# boxing.net
KiCad netlist of a schematic drawn in Altium Designer
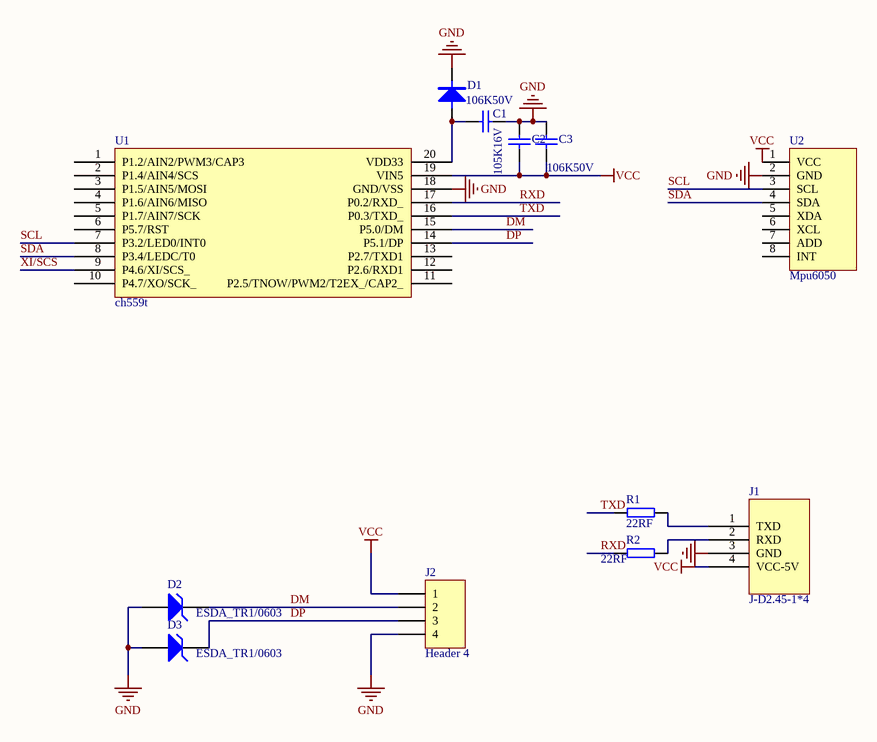
[diagram p0: boxing.SchDoc]

(export (version "E")
  (design (tool "Eeschema 10.0.6"))
  (components
    (comp (ref "C1")
      (value "106K50V")
      (footprint "C0603")
      (description "贴片电容-陶瓷")
      (libsource (lib "Capacitor") (part "C0603X7R-106K50V"))
    )
    (comp (ref "C2")
      (value "105K16V")
      (footprint "C0603")
      (description "贴片电容-陶瓷")
      (libsource (lib "Capacitor") (part "C0603X7R-105K16V"))
    )
    (comp (ref "C3")
      (value "106K50V")
      (footprint "C0603")
      (description "贴片电容-陶瓷")
      (libsource (lib "Capacitor") (part "C0603X7R-106K50V"))
    )
    (comp (ref "D1")
      (value "500mA/13.2V")
      (footprint "D1206")
      (description "500mA/13.2V 自恢复保险丝")
      (libsource (lib "Diode") (part "1206MSD"))
    )
    (comp (ref "D2")
      (value "ESDA_TR1/0603")
      (footprint "HS_0603D")
      (description "Zener Diode")
      (fields (field (name "PUBLISHER") "*"))
      (libsource (lib "HSC32K1(QFN56)_BlueTooth_V2.0_20171108 - 副本") (part "D Zener"))
    )
    (comp (ref "D3")
      (value "ESDA_TR1/0603")
      (footprint "HS_0603D")
      (description "Zener Diode")
      (fields (field (name "PUBLISHER") "*"))
      (libsource (lib "HSC32K1(QFN56)_BlueTooth_V2.0_20171108 - 副本") (part "D Zener"))
    )
    (comp (ref "J1")
      (value "J-D2.45-1*4")
      (footprint "D2.54-1*4P")
      (libsource (lib "Connector") (part "J-D2.54-1*4单排排母"))
    )
    (comp (ref "J2")
      (value "Header 4")
      (footprint "USB-AB")
      (description "Header, 4-Pin")
      (fields (field (name "PUBLISHER") "Altium Limited"))
      (libsource (lib "Miscellaneous Connectors") (part "Header 4"))
    )
    (comp (ref "R1")
      (value "22RF")
      (footprint "R0603")
      (description "贴片电阻-通用")
      (libsource (lib "Resistor") (part "R0603-22RF"))
    )
    (comp (ref "R2")
      (value "22RF")
      (footprint "R0603")
      (description "贴片电阻-通用")
      (libsource (lib "Resistor") (part "R0603-22RF"))
    )
    (comp (ref "U1")
      (value "ch559t")
      (footprint "SSOP-20")
      (description "CH559T-20pin")
      (libsource (lib "IC") (part "CH559T"))
    )
    (comp (ref "U2") (value "Mpu6050") (libsource (lib "IC") (part "Mpu6050")))
  )
  (nets
    (net (code "1") (name "/DM") (class "Default")
      (node (ref "D2") (pin "2") (pinfunction "K_2") (pintype "passive"))
      (node (ref "J2") (pin "2") (pinfunction "2_2") (pintype "passive"))
      (node (ref "U1") (pin "15") (pinfunction "P5.0/DM_15") (pintype "passive"))
    )
    (net (code "2") (name "/DP") (class "Default")
      (node (ref "D3") (pin "2") (pinfunction "K_2") (pintype "passive"))
      (node (ref "J2") (pin "3") (pinfunction "3_3") (pintype "passive"))
      (node (ref "U1") (pin "14") (pinfunction "P5.1/DP_14") (pintype "passive"))
    )
    (net (code "3") (name "/RXD") (class "Default")
      (node (ref "R2") (pin "2") (pinfunction "2_2") (pintype "passive"))
      (node (ref "U1") (pin "17") (pinfunction "P0.2/RXD__17") (pintype "passive"))
    )
    (net (code "4") (name "/SCL") (class "Default")
      (node (ref "U1") (pin "7") (pinfunction "P3.2/LED0/INT0_7") (pintype "passive"))
      (node (ref "U2") (pin "3") (pinfunction "SCL_3") (pintype "passive"))
    )
    (net (code "5") (name "/SDA") (class "Default")
      (node (ref "U1") (pin "8") (pinfunction "P3.4/LEDC/T0_8") (pintype "passive"))
      (node (ref "U2") (pin "4") (pinfunction "SDA_4") (pintype "passive"))
    )
    (net (code "6") (name "/TXD") (class "Default")
      (node (ref "R1") (pin "2") (pinfunction "2_2") (pintype "passive"))
      (node (ref "U1") (pin "16") (pinfunction "P0.3/TXD__16") (pintype "passive"))
    )
    (net (code "7") (name "/XI{slash}SCS") (class "Default")
      (node (ref "U1") (pin "9") (pinfunction "P4.6/XI/SCS__9") (pintype "passive"))
    )
    (net (code "8") (name "DGND") (class "Default")
      (node (ref "J1") (pin "3") (pinfunction "GND_3") (pintype "passive"))
    )
    (net (code "9") (name "GND") (class "Default")
      (node (ref "C1") (pin "1") (pinfunction "1_1") (pintype "passive"))
      (node (ref "C2") (pin "1") (pinfunction "1_1") (pintype "passive"))
      (node (ref "C3") (pin "1") (pinfunction "1_1") (pintype "passive"))
      (node (ref "D1") (pin "2") (pinfunction "2_2") (pintype "passive"))
      (node (ref "D2") (pin "1") (pinfunction "A_1") (pintype "passive"))
      (node (ref "D3") (pin "1") (pinfunction "A_1") (pintype "passive"))
      (node (ref "J2") (pin "4") (pinfunction "4_4") (pintype "passive"))
      (node (ref "U1") (pin "18") (pinfunction "GND/VSS_18") (pintype "passive"))
      (node (ref "U2") (pin "2") (pinfunction "GND_2") (pintype "passive"))
    )
    (net (code "10") (name "Net-(J1-RXD)") (class "Default")
      (node (ref "J1") (pin "2") (pinfunction "RXD_2") (pintype "passive"))
      (node (ref "R2") (pin "1") (pinfunction "1_1") (pintype "passive"))
    )
    (net (code "11") (name "Net-(J1-TXD)") (class "Default")
      (node (ref "J1") (pin "1") (pinfunction "TXD_1") (pintype "passive"))
      (node (ref "R1") (pin "1") (pinfunction "1_1") (pintype "passive"))
    )
    (net (code "12") (name "Net-(U1-VDD33)") (class "Default")
      (node (ref "C1") (pin "2") (pinfunction "2_2") (pintype "passive"))
      (node (ref "D1") (pin "1") (pinfunction "1_1") (pintype "passive"))
      (node (ref "U1") (pin "20") (pinfunction "VDD33_20") (pintype "passive"))
    )
    (net (code "13") (name "VCC") (class "Default")
      (node (ref "C2") (pin "2") (pinfunction "2_2") (pintype "passive"))
      (node (ref "C3") (pin "2") (pinfunction "2_2") (pintype "passive"))
      (node (ref "J1") (pin "4") (pinfunction "VCC-5V_4") (pintype "passive"))
      (node (ref "J2") (pin "1") (pinfunction "1_1") (pintype "passive"))
      (node (ref "U1") (pin "19") (pinfunction "VIN5_19") (pintype "passive"))
      (node (ref "U2") (pin "1") (pinfunction "VCC_1") (pintype "passive"))
    )
    (net (code "14") (name "unconnected-(U1-P1.2{slash}AIN2{slash}PWM3{slash}CAP3-Pad1)") (class "Default")
      (node (ref "U1") (pin "1") (pinfunction "P1.2/AIN2/PWM3/CAP3_1") (pintype "passive"))
    )
    (net (code "15") (name "unconnected-(U1-P1.4{slash}AIN4{slash}SCS-Pad2)") (class "Default")
      (node (ref "U1") (pin "2") (pinfunction "P1.4/AIN4/SCS_2") (pintype "passive"))
    )
    (net (code "16") (name "unconnected-(U1-P1.5{slash}AIN5{slash}MOSI-Pad3)") (class "Default")
      (node (ref "U1") (pin "3") (pinfunction "P1.5/AIN5/MOSI_3") (pintype "passive"))
    )
    (net (code "17") (name "unconnected-(U1-P1.6{slash}AIN6{slash}MISO-Pad4)") (class "Default")
      (node (ref "U1") (pin "4") (pinfunction "P1.6/AIN6/MISO_4") (pintype "passive"))
    )
    (net (code "18") (name "unconnected-(U1-P1.7{slash}AIN7{slash}SCK-Pad5)") (class "Default")
      (node (ref "U1") (pin "5") (pinfunction "P1.7/AIN7/SCK_5") (pintype "passive"))
    )
    (net (code "19") (name "unconnected-(U1-P2.5{slash}TNOW{slash}PWM2{slash}T2EX_{slash}CAP2_-Pad11)") (class "Default")
      (node (ref "U1") (pin "11") (pinfunction "P2.5/TNOW/PWM2/T2EX_/CAP2__11") (pintype "passive"))
    )
    (net (code "20") (name "unconnected-(U1-P2.6{slash}RXD1-Pad12)") (class "Default")
      (node (ref "U1") (pin "12") (pinfunction "P2.6/RXD1_12") (pintype "passive"))
    )
    (net (code "21") (name "unconnected-(U1-P2.7{slash}TXD1-Pad13)") (class "Default")
      (node (ref "U1") (pin "13") (pinfunction "P2.7/TXD1_13") (pintype "passive"))
    )
    (net (code "22") (name "unconnected-(U1-P4.7{slash}XO{slash}SCK_-Pad10)") (class "Default")
      (node (ref "U1") (pin "10") (pinfunction "P4.7/XO/SCK__10") (pintype "passive"))
    )
    (net (code "23") (name "unconnected-(U1-P5.7{slash}RST-Pad6)") (class "Default")
      (node (ref "U1") (pin "6") (pinfunction "P5.7/RST_6") (pintype "passive"))
    )
    (net (code "24") (name "unconnected-(U2-ADD-Pad7)") (class "Default")
      (node (ref "U2") (pin "7") (pinfunction "ADD_7") (pintype "passive"))
    )
    (net (code "25") (name "unconnected-(U2-INT-Pad8)") (class "Default")
      (node (ref "U2") (pin "8") (pinfunction "INT_8") (pintype "passive"))
    )
    (net (code "26") (name "unconnected-(U2-XCL-Pad6)") (class "Default")
      (node (ref "U2") (pin "6") (pinfunction "XCL_6") (pintype "passive"))
    )
    (net (code "27") (name "unconnected-(U2-XDA-Pad5)") (class "Default")
      (node (ref "U2") (pin "5") (pinfunction "XDA_5") (pintype "passive"))
    )
  )
)
